# Matrix.net
KiCad netlist of a schematic drawn in Altium Designer
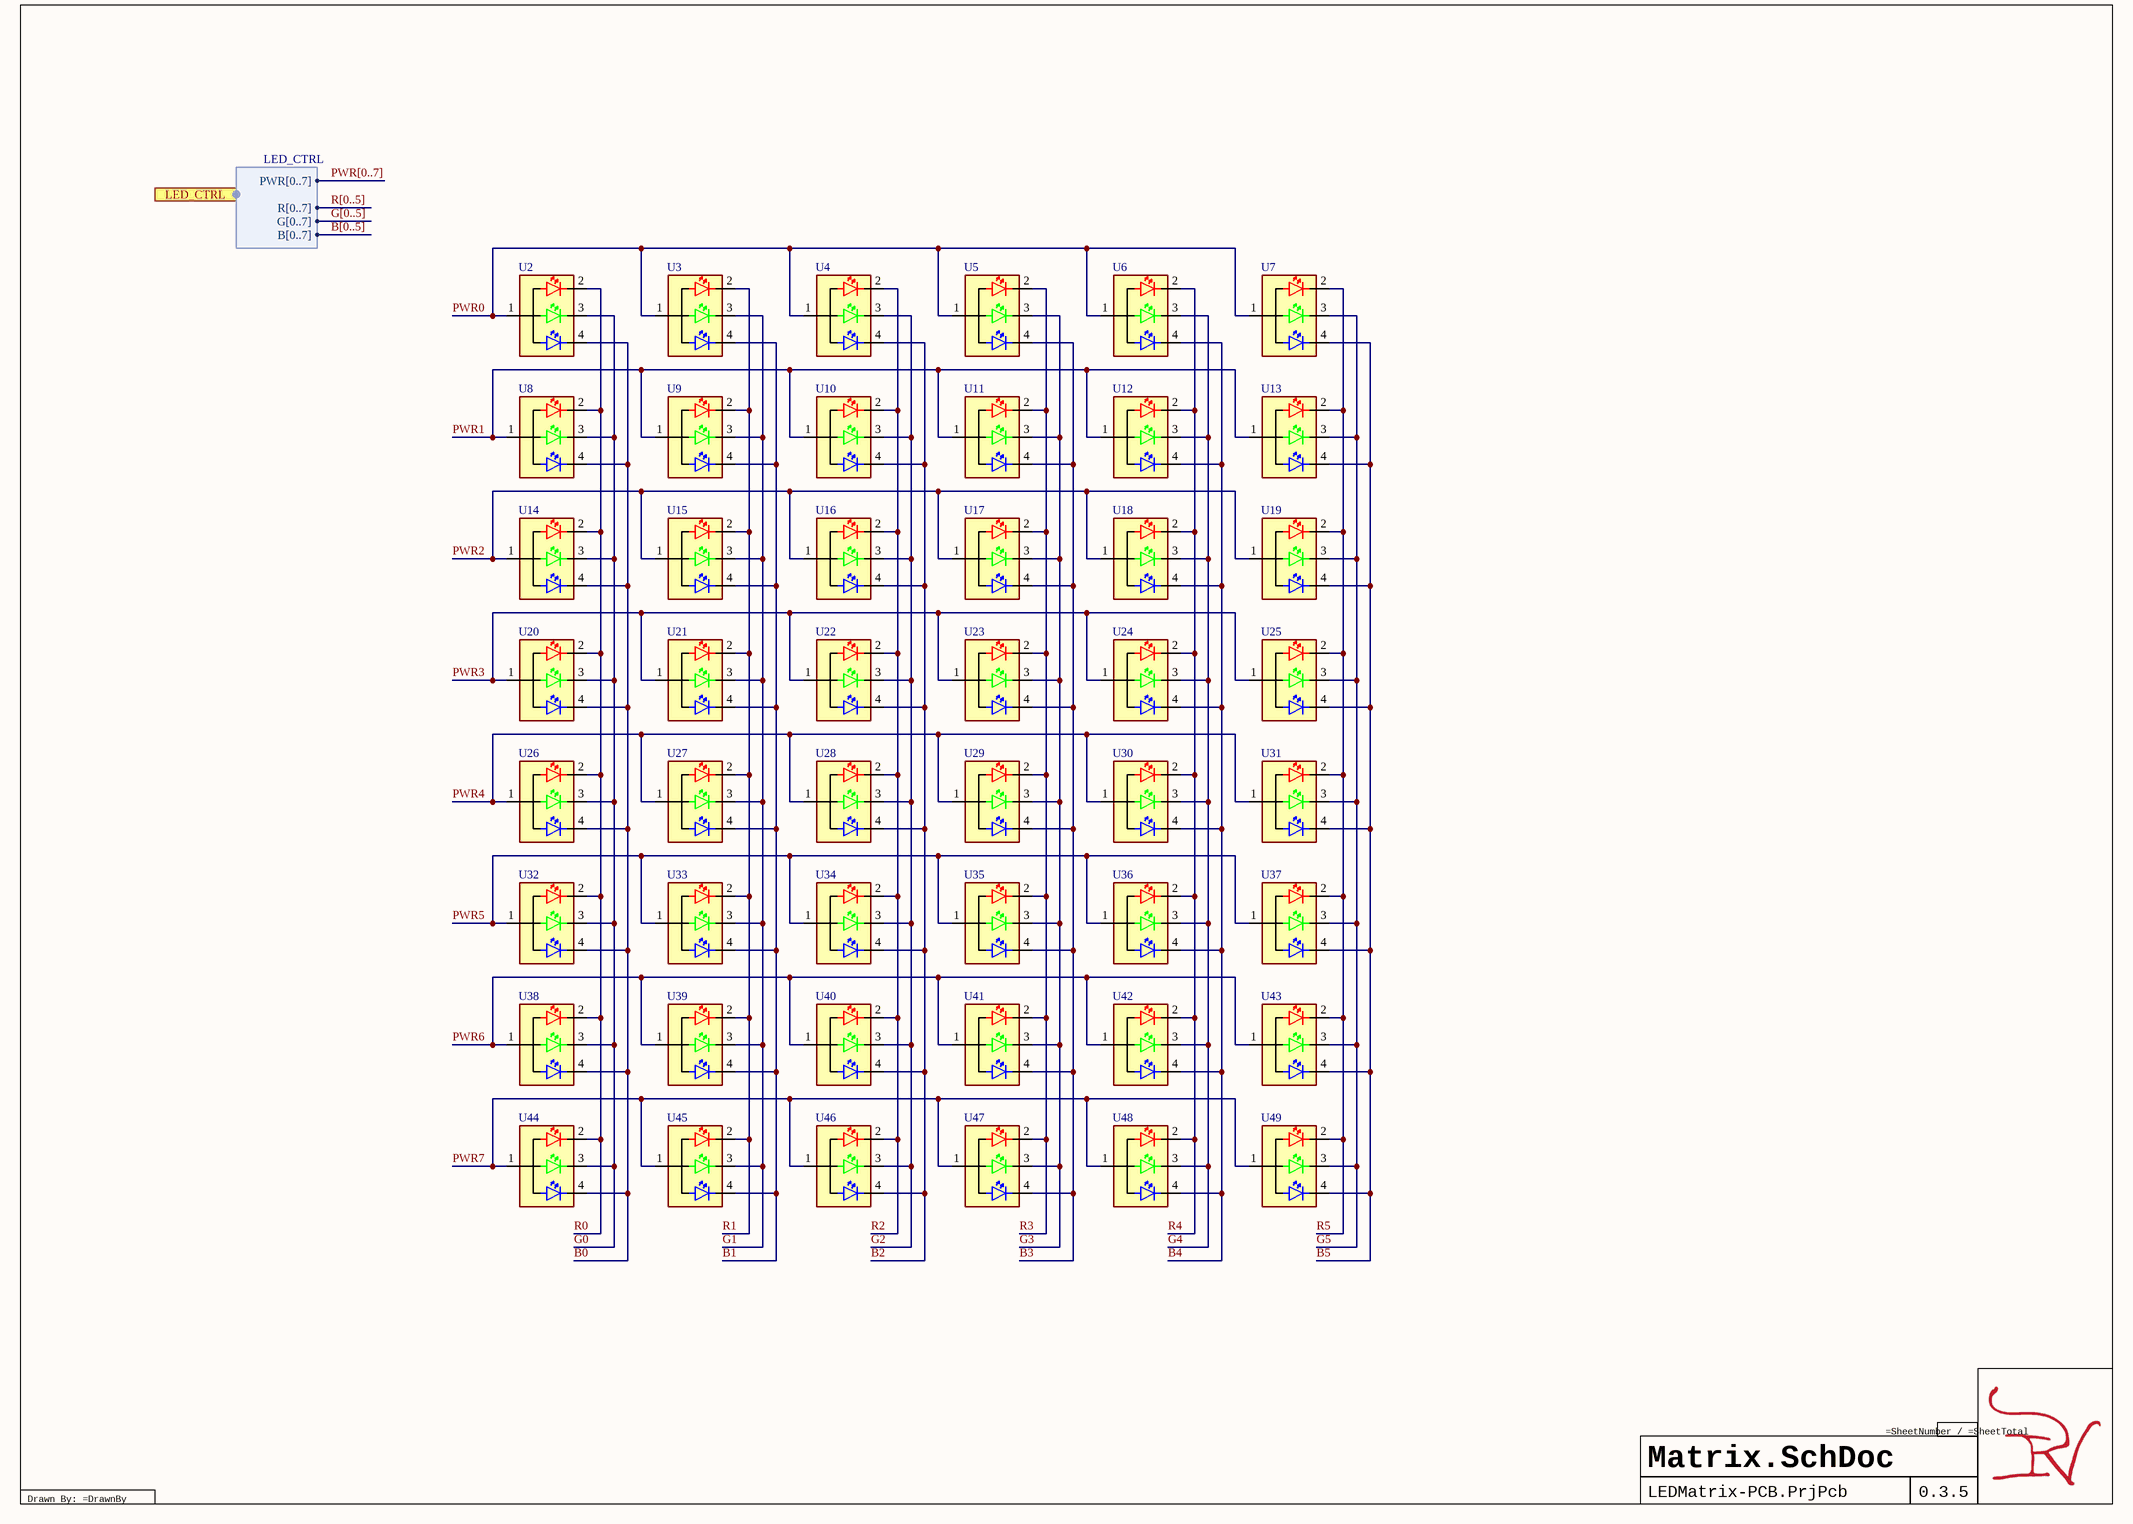
[diagram p0: Matrix.SchDoc]

(export (version "E")
  (design (tool "Eeschema 10.0.6"))
  (components
    (comp (ref "U2")
      (value "B36J3RGB-F6C0001H4U1930")
      (footprint "B36J3RGB-F6C0001H4U1930-Footprint-1")
      (description "Led Rgb Common Anode (0.65(L)X 0")
      (libsource (lib "IIT Motorsports") (part "B36J3RGB-F6C0001H4U1930-Symbol-1"))
    )
    (comp (ref "U3")
      (value "B36J3RGB-F6C0001H4U1930")
      (footprint "B36J3RGB-F6C0001H4U1930-Footprint-1")
      (description "Led Rgb Common Anode (0.65(L)X 0")
      (libsource (lib "IIT Motorsports") (part "B36J3RGB-F6C0001H4U1930-Symbol-1"))
    )
    (comp (ref "U4")
      (value "B36J3RGB-F6C0001H4U1930")
      (footprint "B36J3RGB-F6C0001H4U1930-Footprint-1")
      (description "Led Rgb Common Anode (0.65(L)X 0")
      (libsource (lib "IIT Motorsports") (part "B36J3RGB-F6C0001H4U1930-Symbol-1"))
    )
    (comp (ref "U5")
      (value "B36J3RGB-F6C0001H4U1930")
      (footprint "B36J3RGB-F6C0001H4U1930-Footprint-1")
      (description "Led Rgb Common Anode (0.65(L)X 0")
      (libsource (lib "IIT Motorsports") (part "B36J3RGB-F6C0001H4U1930-Symbol-1"))
    )
    (comp (ref "U6")
      (value "B36J3RGB-F6C0001H4U1930")
      (footprint "B36J3RGB-F6C0001H4U1930-Footprint-1")
      (description "Led Rgb Common Anode (0.65(L)X 0")
      (libsource (lib "IIT Motorsports") (part "B36J3RGB-F6C0001H4U1930-Symbol-1"))
    )
    (comp (ref "U7")
      (value "B36J3RGB-F6C0001H4U1930")
      (footprint "B36J3RGB-F6C0001H4U1930-Footprint-1")
      (description "Led Rgb Common Anode (0.65(L)X 0")
      (libsource (lib "IIT Motorsports") (part "B36J3RGB-F6C0001H4U1930-Symbol-1"))
    )
    (comp (ref "U8")
      (value "B36J3RGB-F6C0001H4U1930")
      (footprint "B36J3RGB-F6C0001H4U1930-Footprint-1")
      (description "Led Rgb Common Anode (0.65(L)X 0")
      (libsource (lib "IIT Motorsports") (part "B36J3RGB-F6C0001H4U1930-Symbol-1"))
    )
    (comp (ref "U9")
      (value "B36J3RGB-F6C0001H4U1930")
      (footprint "B36J3RGB-F6C0001H4U1930-Footprint-1")
      (description "Led Rgb Common Anode (0.65(L)X 0")
      (libsource (lib "IIT Motorsports") (part "B36J3RGB-F6C0001H4U1930-Symbol-1"))
    )
    (comp (ref "U10")
      (value "B36J3RGB-F6C0001H4U1930")
      (footprint "B36J3RGB-F6C0001H4U1930-Footprint-1")
      (description "Led Rgb Common Anode (0.65(L)X 0")
      (libsource (lib "IIT Motorsports") (part "B36J3RGB-F6C0001H4U1930-Symbol-1"))
    )
    (comp (ref "U11")
      (value "B36J3RGB-F6C0001H4U1930")
      (footprint "B36J3RGB-F6C0001H4U1930-Footprint-1")
      (description "Led Rgb Common Anode (0.65(L)X 0")
      (libsource (lib "IIT Motorsports") (part "B36J3RGB-F6C0001H4U1930-Symbol-1"))
    )
    (comp (ref "U12")
      (value "B36J3RGB-F6C0001H4U1930")
      (footprint "B36J3RGB-F6C0001H4U1930-Footprint-1")
      (description "Led Rgb Common Anode (0.65(L)X 0")
      (libsource (lib "IIT Motorsports") (part "B36J3RGB-F6C0001H4U1930-Symbol-1"))
    )
    (comp (ref "U13")
      (value "B36J3RGB-F6C0001H4U1930")
      (footprint "B36J3RGB-F6C0001H4U1930-Footprint-1")
      (description "Led Rgb Common Anode (0.65(L)X 0")
      (libsource (lib "IIT Motorsports") (part "B36J3RGB-F6C0001H4U1930-Symbol-1"))
    )
    (comp (ref "U14")
      (value "B36J3RGB-F6C0001H4U1930")
      (footprint "B36J3RGB-F6C0001H4U1930-Footprint-1")
      (description "Led Rgb Common Anode (0.65(L)X 0")
      (libsource (lib "IIT Motorsports") (part "B36J3RGB-F6C0001H4U1930-Symbol-1"))
    )
    (comp (ref "U15")
      (value "B36J3RGB-F6C0001H4U1930")
      (footprint "B36J3RGB-F6C0001H4U1930-Footprint-1")
      (description "Led Rgb Common Anode (0.65(L)X 0")
      (libsource (lib "IIT Motorsports") (part "B36J3RGB-F6C0001H4U1930-Symbol-1"))
    )
    (comp (ref "U16")
      (value "B36J3RGB-F6C0001H4U1930")
      (footprint "B36J3RGB-F6C0001H4U1930-Footprint-1")
      (description "Led Rgb Common Anode (0.65(L)X 0")
      (libsource (lib "IIT Motorsports") (part "B36J3RGB-F6C0001H4U1930-Symbol-1"))
    )
    (comp (ref "U17")
      (value "B36J3RGB-F6C0001H4U1930")
      (footprint "B36J3RGB-F6C0001H4U1930-Footprint-1")
      (description "Led Rgb Common Anode (0.65(L)X 0")
      (libsource (lib "IIT Motorsports") (part "B36J3RGB-F6C0001H4U1930-Symbol-1"))
    )
    (comp (ref "U18")
      (value "B36J3RGB-F6C0001H4U1930")
      (footprint "B36J3RGB-F6C0001H4U1930-Footprint-1")
      (description "Led Rgb Common Anode (0.65(L)X 0")
      (libsource (lib "IIT Motorsports") (part "B36J3RGB-F6C0001H4U1930-Symbol-1"))
    )
    (comp (ref "U19")
      (value "B36J3RGB-F6C0001H4U1930")
      (footprint "B36J3RGB-F6C0001H4U1930-Footprint-1")
      (description "Led Rgb Common Anode (0.65(L)X 0")
      (libsource (lib "IIT Motorsports") (part "B36J3RGB-F6C0001H4U1930-Symbol-1"))
    )
    (comp (ref "U20")
      (value "B36J3RGB-F6C0001H4U1930")
      (footprint "B36J3RGB-F6C0001H4U1930-Footprint-1")
      (description "Led Rgb Common Anode (0.65(L)X 0")
      (libsource (lib "IIT Motorsports") (part "B36J3RGB-F6C0001H4U1930-Symbol-1"))
    )
    (comp (ref "U21")
      (value "B36J3RGB-F6C0001H4U1930")
      (footprint "B36J3RGB-F6C0001H4U1930-Footprint-1")
      (description "Led Rgb Common Anode (0.65(L)X 0")
      (libsource (lib "IIT Motorsports") (part "B36J3RGB-F6C0001H4U1930-Symbol-1"))
    )
    (comp (ref "U22")
      (value "B36J3RGB-F6C0001H4U1930")
      (footprint "B36J3RGB-F6C0001H4U1930-Footprint-1")
      (description "Led Rgb Common Anode (0.65(L)X 0")
      (libsource (lib "IIT Motorsports") (part "B36J3RGB-F6C0001H4U1930-Symbol-1"))
    )
    (comp (ref "U23")
      (value "B36J3RGB-F6C0001H4U1930")
      (footprint "B36J3RGB-F6C0001H4U1930-Footprint-1")
      (description "Led Rgb Common Anode (0.65(L)X 0")
      (libsource (lib "IIT Motorsports") (part "B36J3RGB-F6C0001H4U1930-Symbol-1"))
    )
    (comp (ref "U24")
      (value "B36J3RGB-F6C0001H4U1930")
      (footprint "B36J3RGB-F6C0001H4U1930-Footprint-1")
      (description "Led Rgb Common Anode (0.65(L)X 0")
      (libsource (lib "IIT Motorsports") (part "B36J3RGB-F6C0001H4U1930-Symbol-1"))
    )
    (comp (ref "U25")
      (value "B36J3RGB-F6C0001H4U1930")
      (footprint "B36J3RGB-F6C0001H4U1930-Footprint-1")
      (description "Led Rgb Common Anode (0.65(L)X 0")
      (libsource (lib "IIT Motorsports") (part "B36J3RGB-F6C0001H4U1930-Symbol-1"))
    )
    (comp (ref "U26")
      (value "B36J3RGB-F6C0001H4U1930")
      (footprint "B36J3RGB-F6C0001H4U1930-Footprint-1")
      (description "Led Rgb Common Anode (0.65(L)X 0")
      (libsource (lib "IIT Motorsports") (part "B36J3RGB-F6C0001H4U1930-Symbol-1"))
    )
    (comp (ref "U27")
      (value "B36J3RGB-F6C0001H4U1930")
      (footprint "B36J3RGB-F6C0001H4U1930-Footprint-1")
      (description "Led Rgb Common Anode (0.65(L)X 0")
      (libsource (lib "IIT Motorsports") (part "B36J3RGB-F6C0001H4U1930-Symbol-1"))
    )
    (comp (ref "U28")
      (value "B36J3RGB-F6C0001H4U1930")
      (footprint "B36J3RGB-F6C0001H4U1930-Footprint-1")
      (description "Led Rgb Common Anode (0.65(L)X 0")
      (libsource (lib "IIT Motorsports") (part "B36J3RGB-F6C0001H4U1930-Symbol-1"))
    )
    (comp (ref "U29")
      (value "B36J3RGB-F6C0001H4U1930")
      (footprint "B36J3RGB-F6C0001H4U1930-Footprint-1")
      (description "Led Rgb Common Anode (0.65(L)X 0")
      (libsource (lib "IIT Motorsports") (part "B36J3RGB-F6C0001H4U1930-Symbol-1"))
    )
    (comp (ref "U30")
      (value "B36J3RGB-F6C0001H4U1930")
      (footprint "B36J3RGB-F6C0001H4U1930-Footprint-1")
      (description "Led Rgb Common Anode (0.65(L)X 0")
      (libsource (lib "IIT Motorsports") (part "B36J3RGB-F6C0001H4U1930-Symbol-1"))
    )
    (comp (ref "U31")
      (value "B36J3RGB-F6C0001H4U1930")
      (footprint "B36J3RGB-F6C0001H4U1930-Footprint-1")
      (description "Led Rgb Common Anode (0.65(L)X 0")
      (libsource (lib "IIT Motorsports") (part "B36J3RGB-F6C0001H4U1930-Symbol-1"))
    )
    (comp (ref "U32")
      (value "B36J3RGB-F6C0001H4U1930")
      (footprint "B36J3RGB-F6C0001H4U1930-Footprint-1")
      (description "Led Rgb Common Anode (0.65(L)X 0")
      (libsource (lib "IIT Motorsports") (part "B36J3RGB-F6C0001H4U1930-Symbol-1"))
    )
    (comp (ref "U33")
      (value "B36J3RGB-F6C0001H4U1930")
      (footprint "B36J3RGB-F6C0001H4U1930-Footprint-1")
      (description "Led Rgb Common Anode (0.65(L)X 0")
      (libsource (lib "IIT Motorsports") (part "B36J3RGB-F6C0001H4U1930-Symbol-1"))
    )
    (comp (ref "U34")
      (value "B36J3RGB-F6C0001H4U1930")
      (footprint "B36J3RGB-F6C0001H4U1930-Footprint-1")
      (description "Led Rgb Common Anode (0.65(L)X 0")
      (libsource (lib "IIT Motorsports") (part "B36J3RGB-F6C0001H4U1930-Symbol-1"))
    )
    (comp (ref "U35")
      (value "B36J3RGB-F6C0001H4U1930")
      (footprint "B36J3RGB-F6C0001H4U1930-Footprint-1")
      (description "Led Rgb Common Anode (0.65(L)X 0")
      (libsource (lib "IIT Motorsports") (part "B36J3RGB-F6C0001H4U1930-Symbol-1"))
    )
    (comp (ref "U36")
      (value "B36J3RGB-F6C0001H4U1930")
      (footprint "B36J3RGB-F6C0001H4U1930-Footprint-1")
      (description "Led Rgb Common Anode (0.65(L)X 0")
      (libsource (lib "IIT Motorsports") (part "B36J3RGB-F6C0001H4U1930-Symbol-1"))
    )
    (comp (ref "U37")
      (value "B36J3RGB-F6C0001H4U1930")
      (footprint "B36J3RGB-F6C0001H4U1930-Footprint-1")
      (description "Led Rgb Common Anode (0.65(L)X 0")
      (libsource (lib "IIT Motorsports") (part "B36J3RGB-F6C0001H4U1930-Symbol-1"))
    )
    (comp (ref "U38")
      (value "B36J3RGB-F6C0001H4U1930")
      (footprint "B36J3RGB-F6C0001H4U1930-Footprint-1")
      (description "Led Rgb Common Anode (0.65(L)X 0")
      (libsource (lib "IIT Motorsports") (part "B36J3RGB-F6C0001H4U1930-Symbol-1"))
    )
    (comp (ref "U39")
      (value "B36J3RGB-F6C0001H4U1930")
      (footprint "B36J3RGB-F6C0001H4U1930-Footprint-1")
      (description "Led Rgb Common Anode (0.65(L)X 0")
      (libsource (lib "IIT Motorsports") (part "B36J3RGB-F6C0001H4U1930-Symbol-1"))
    )
    (comp (ref "U40")
      (value "B36J3RGB-F6C0001H4U1930")
      (footprint "B36J3RGB-F6C0001H4U1930-Footprint-1")
      (description "Led Rgb Common Anode (0.65(L)X 0")
      (libsource (lib "IIT Motorsports") (part "B36J3RGB-F6C0001H4U1930-Symbol-1"))
    )
    (comp (ref "U41")
      (value "B36J3RGB-F6C0001H4U1930")
      (footprint "B36J3RGB-F6C0001H4U1930-Footprint-1")
      (description "Led Rgb Common Anode (0.65(L)X 0")
      (libsource (lib "IIT Motorsports") (part "B36J3RGB-F6C0001H4U1930-Symbol-1"))
    )
    (comp (ref "U42")
      (value "B36J3RGB-F6C0001H4U1930")
      (footprint "B36J3RGB-F6C0001H4U1930-Footprint-1")
      (description "Led Rgb Common Anode (0.65(L)X 0")
      (libsource (lib "IIT Motorsports") (part "B36J3RGB-F6C0001H4U1930-Symbol-1"))
    )
    (comp (ref "U43")
      (value "B36J3RGB-F6C0001H4U1930")
      (footprint "B36J3RGB-F6C0001H4U1930-Footprint-1")
      (description "Led Rgb Common Anode (0.65(L)X 0")
      (libsource (lib "IIT Motorsports") (part "B36J3RGB-F6C0001H4U1930-Symbol-1"))
    )
    (comp (ref "U44")
      (value "B36J3RGB-F6C0001H4U1930")
      (footprint "B36J3RGB-F6C0001H4U1930-Footprint-1")
      (description "Led Rgb Common Anode (0.65(L)X 0")
      (libsource (lib "IIT Motorsports") (part "B36J3RGB-F6C0001H4U1930-Symbol-1"))
    )
    (comp (ref "U45")
      (value "B36J3RGB-F6C0001H4U1930")
      (footprint "B36J3RGB-F6C0001H4U1930-Footprint-1")
      (description "Led Rgb Common Anode (0.65(L)X 0")
      (libsource (lib "IIT Motorsports") (part "B36J3RGB-F6C0001H4U1930-Symbol-1"))
    )
    (comp (ref "U46")
      (value "B36J3RGB-F6C0001H4U1930")
      (footprint "B36J3RGB-F6C0001H4U1930-Footprint-1")
      (description "Led Rgb Common Anode (0.65(L)X 0")
      (libsource (lib "IIT Motorsports") (part "B36J3RGB-F6C0001H4U1930-Symbol-1"))
    )
    (comp (ref "U47")
      (value "B36J3RGB-F6C0001H4U1930")
      (footprint "B36J3RGB-F6C0001H4U1930-Footprint-1")
      (description "Led Rgb Common Anode (0.65(L)X 0")
      (libsource (lib "IIT Motorsports") (part "B36J3RGB-F6C0001H4U1930-Symbol-1"))
    )
    (comp (ref "U48")
      (value "B36J3RGB-F6C0001H4U1930")
      (footprint "B36J3RGB-F6C0001H4U1930-Footprint-1")
      (description "Led Rgb Common Anode (0.65(L)X 0")
      (libsource (lib "IIT Motorsports") (part "B36J3RGB-F6C0001H4U1930-Symbol-1"))
    )
    (comp (ref "U49")
      (value "B36J3RGB-F6C0001H4U1930")
      (footprint "B36J3RGB-F6C0001H4U1930-Footprint-1")
      (description "Led Rgb Common Anode (0.65(L)X 0")
      (libsource (lib "IIT Motorsports") (part "B36J3RGB-F6C0001H4U1930-Symbol-1"))
    )
  )
  (nets
    (net (code "2") (name "/B0") (class "Default")
      (node (ref "U14") (pin "4") (pinfunction "4_4") (pintype "passive"))
      (node (ref "U2") (pin "4") (pinfunction "4_4") (pintype "passive"))
      (node (ref "U20") (pin "4") (pinfunction "4_4") (pintype "passive"))
      (node (ref "U26") (pin "4") (pinfunction "4_4") (pintype "passive"))
      (node (ref "U32") (pin "4") (pinfunction "4_4") (pintype "passive"))
      (node (ref "U38") (pin "4") (pinfunction "4_4") (pintype "passive"))
      (node (ref "U44") (pin "4") (pinfunction "4_4") (pintype "passive"))
      (node (ref "U8") (pin "4") (pinfunction "4_4") (pintype "passive"))
    )
    (net (code "3") (name "/B1") (class "Default")
      (node (ref "U15") (pin "4") (pinfunction "4_4") (pintype "passive"))
      (node (ref "U21") (pin "4") (pinfunction "4_4") (pintype "passive"))
      (node (ref "U27") (pin "4") (pinfunction "4_4") (pintype "passive"))
      (node (ref "U3") (pin "4") (pinfunction "4_4") (pintype "passive"))
      (node (ref "U33") (pin "4") (pinfunction "4_4") (pintype "passive"))
      (node (ref "U39") (pin "4") (pinfunction "4_4") (pintype "passive"))
      (node (ref "U45") (pin "4") (pinfunction "4_4") (pintype "passive"))
      (node (ref "U9") (pin "4") (pinfunction "4_4") (pintype "passive"))
    )
    (net (code "4") (name "/B2") (class "Default")
      (node (ref "U10") (pin "4") (pinfunction "4_4") (pintype "passive"))
      (node (ref "U16") (pin "4") (pinfunction "4_4") (pintype "passive"))
      (node (ref "U22") (pin "4") (pinfunction "4_4") (pintype "passive"))
      (node (ref "U28") (pin "4") (pinfunction "4_4") (pintype "passive"))
      (node (ref "U34") (pin "4") (pinfunction "4_4") (pintype "passive"))
      (node (ref "U4") (pin "4") (pinfunction "4_4") (pintype "passive"))
      (node (ref "U40") (pin "4") (pinfunction "4_4") (pintype "passive"))
      (node (ref "U46") (pin "4") (pinfunction "4_4") (pintype "passive"))
    )
    (net (code "5") (name "/B3") (class "Default")
      (node (ref "U11") (pin "4") (pinfunction "4_4") (pintype "passive"))
      (node (ref "U17") (pin "4") (pinfunction "4_4") (pintype "passive"))
      (node (ref "U23") (pin "4") (pinfunction "4_4") (pintype "passive"))
      (node (ref "U29") (pin "4") (pinfunction "4_4") (pintype "passive"))
      (node (ref "U35") (pin "4") (pinfunction "4_4") (pintype "passive"))
      (node (ref "U41") (pin "4") (pinfunction "4_4") (pintype "passive"))
      (node (ref "U47") (pin "4") (pinfunction "4_4") (pintype "passive"))
      (node (ref "U5") (pin "4") (pinfunction "4_4") (pintype "passive"))
    )
    (net (code "6") (name "/B4") (class "Default")
      (node (ref "U12") (pin "4") (pinfunction "4_4") (pintype "passive"))
      (node (ref "U18") (pin "4") (pinfunction "4_4") (pintype "passive"))
      (node (ref "U24") (pin "4") (pinfunction "4_4") (pintype "passive"))
      (node (ref "U30") (pin "4") (pinfunction "4_4") (pintype "passive"))
      (node (ref "U36") (pin "4") (pinfunction "4_4") (pintype "passive"))
      (node (ref "U42") (pin "4") (pinfunction "4_4") (pintype "passive"))
      (node (ref "U48") (pin "4") (pinfunction "4_4") (pintype "passive"))
      (node (ref "U6") (pin "4") (pinfunction "4_4") (pintype "passive"))
    )
    (net (code "7") (name "/B5") (class "Default")
      (node (ref "U13") (pin "4") (pinfunction "4_4") (pintype "passive"))
      (node (ref "U19") (pin "4") (pinfunction "4_4") (pintype "passive"))
      (node (ref "U25") (pin "4") (pinfunction "4_4") (pintype "passive"))
      (node (ref "U31") (pin "4") (pinfunction "4_4") (pintype "passive"))
      (node (ref "U37") (pin "4") (pinfunction "4_4") (pintype "passive"))
      (node (ref "U43") (pin "4") (pinfunction "4_4") (pintype "passive"))
      (node (ref "U49") (pin "4") (pinfunction "4_4") (pintype "passive"))
      (node (ref "U7") (pin "4") (pinfunction "4_4") (pintype "passive"))
    )
    (net (code "9") (name "/G0") (class "Default")
      (node (ref "U14") (pin "3") (pinfunction "3_3") (pintype "passive"))
      (node (ref "U2") (pin "3") (pinfunction "3_3") (pintype "passive"))
      (node (ref "U20") (pin "3") (pinfunction "3_3") (pintype "passive"))
      (node (ref "U26") (pin "3") (pinfunction "3_3") (pintype "passive"))
      (node (ref "U32") (pin "3") (pinfunction "3_3") (pintype "passive"))
      (node (ref "U38") (pin "3") (pinfunction "3_3") (pintype "passive"))
      (node (ref "U44") (pin "3") (pinfunction "3_3") (pintype "passive"))
      (node (ref "U8") (pin "3") (pinfunction "3_3") (pintype "passive"))
    )
    (net (code "10") (name "/G1") (class "Default")
      (node (ref "U15") (pin "3") (pinfunction "3_3") (pintype "passive"))
      (node (ref "U21") (pin "3") (pinfunction "3_3") (pintype "passive"))
      (node (ref "U27") (pin "3") (pinfunction "3_3") (pintype "passive"))
      (node (ref "U3") (pin "3") (pinfunction "3_3") (pintype "passive"))
      (node (ref "U33") (pin "3") (pinfunction "3_3") (pintype "passive"))
      (node (ref "U39") (pin "3") (pinfunction "3_3") (pintype "passive"))
      (node (ref "U45") (pin "3") (pinfunction "3_3") (pintype "passive"))
      (node (ref "U9") (pin "3") (pinfunction "3_3") (pintype "passive"))
    )
    (net (code "11") (name "/G2") (class "Default")
      (node (ref "U10") (pin "3") (pinfunction "3_3") (pintype "passive"))
      (node (ref "U16") (pin "3") (pinfunction "3_3") (pintype "passive"))
      (node (ref "U22") (pin "3") (pinfunction "3_3") (pintype "passive"))
      (node (ref "U28") (pin "3") (pinfunction "3_3") (pintype "passive"))
      (node (ref "U34") (pin "3") (pinfunction "3_3") (pintype "passive"))
      (node (ref "U4") (pin "3") (pinfunction "3_3") (pintype "passive"))
      (node (ref "U40") (pin "3") (pinfunction "3_3") (pintype "passive"))
      (node (ref "U46") (pin "3") (pinfunction "3_3") (pintype "passive"))
    )
    (net (code "12") (name "/G3") (class "Default")
      (node (ref "U11") (pin "3") (pinfunction "3_3") (pintype "passive"))
      (node (ref "U17") (pin "3") (pinfunction "3_3") (pintype "passive"))
      (node (ref "U23") (pin "3") (pinfunction "3_3") (pintype "passive"))
      (node (ref "U29") (pin "3") (pinfunction "3_3") (pintype "passive"))
      (node (ref "U35") (pin "3") (pinfunction "3_3") (pintype "passive"))
      (node (ref "U41") (pin "3") (pinfunction "3_3") (pintype "passive"))
      (node (ref "U47") (pin "3") (pinfunction "3_3") (pintype "passive"))
      (node (ref "U5") (pin "3") (pinfunction "3_3") (pintype "passive"))
    )
    (net (code "13") (name "/G4") (class "Default")
      (node (ref "U12") (pin "3") (pinfunction "3_3") (pintype "passive"))
      (node (ref "U18") (pin "3") (pinfunction "3_3") (pintype "passive"))
      (node (ref "U24") (pin "3") (pinfunction "3_3") (pintype "passive"))
      (node (ref "U30") (pin "3") (pinfunction "3_3") (pintype "passive"))
      (node (ref "U36") (pin "3") (pinfunction "3_3") (pintype "passive"))
      (node (ref "U42") (pin "3") (pinfunction "3_3") (pintype "passive"))
      (node (ref "U48") (pin "3") (pinfunction "3_3") (pintype "passive"))
      (node (ref "U6") (pin "3") (pinfunction "3_3") (pintype "passive"))
    )
    (net (code "14") (name "/G5") (class "Default")
      (node (ref "U13") (pin "3") (pinfunction "3_3") (pintype "passive"))
      (node (ref "U19") (pin "3") (pinfunction "3_3") (pintype "passive"))
      (node (ref "U25") (pin "3") (pinfunction "3_3") (pintype "passive"))
      (node (ref "U31") (pin "3") (pinfunction "3_3") (pintype "passive"))
      (node (ref "U37") (pin "3") (pinfunction "3_3") (pintype "passive"))
      (node (ref "U43") (pin "3") (pinfunction "3_3") (pintype "passive"))
      (node (ref "U49") (pin "3") (pinfunction "3_3") (pintype "passive"))
      (node (ref "U7") (pin "3") (pinfunction "3_3") (pintype "passive"))
    )
    (net (code "17") (name "/PWR0") (class "Default")
      (node (ref "U2") (pin "1") (pinfunction "1_1") (pintype "passive"))
      (node (ref "U3") (pin "1") (pinfunction "1_1") (pintype "passive"))
      (node (ref "U4") (pin "1") (pinfunction "1_1") (pintype "passive"))
      (node (ref "U5") (pin "1") (pinfunction "1_1") (pintype "passive"))
      (node (ref "U6") (pin "1") (pinfunction "1_1") (pintype "passive"))
      (node (ref "U7") (pin "1") (pinfunction "1_1") (pintype "passive"))
    )
    (net (code "18") (name "/PWR1") (class "Default")
      (node (ref "U10") (pin "1") (pinfunction "1_1") (pintype "passive"))
      (node (ref "U11") (pin "1") (pinfunction "1_1") (pintype "passive"))
      (node (ref "U12") (pin "1") (pinfunction "1_1") (pintype "passive"))
      (node (ref "U13") (pin "1") (pinfunction "1_1") (pintype "passive"))
      (node (ref "U8") (pin "1") (pinfunction "1_1") (pintype "passive"))
      (node (ref "U9") (pin "1") (pinfunction "1_1") (pintype "passive"))
    )
    (net (code "19") (name "/PWR2") (class "Default")
      (node (ref "U14") (pin "1") (pinfunction "1_1") (pintype "passive"))
      (node (ref "U15") (pin "1") (pinfunction "1_1") (pintype "passive"))
      (node (ref "U16") (pin "1") (pinfunction "1_1") (pintype "passive"))
      (node (ref "U17") (pin "1") (pinfunction "1_1") (pintype "passive"))
      (node (ref "U18") (pin "1") (pinfunction "1_1") (pintype "passive"))
      (node (ref "U19") (pin "1") (pinfunction "1_1") (pintype "passive"))
    )
    (net (code "20") (name "/PWR3") (class "Default")
      (node (ref "U20") (pin "1") (pinfunction "1_1") (pintype "passive"))
      (node (ref "U21") (pin "1") (pinfunction "1_1") (pintype "passive"))
      (node (ref "U22") (pin "1") (pinfunction "1_1") (pintype "passive"))
      (node (ref "U23") (pin "1") (pinfunction "1_1") (pintype "passive"))
      (node (ref "U24") (pin "1") (pinfunction "1_1") (pintype "passive"))
      (node (ref "U25") (pin "1") (pinfunction "1_1") (pintype "passive"))
    )
    (net (code "21") (name "/PWR4") (class "Default")
      (node (ref "U26") (pin "1") (pinfunction "1_1") (pintype "passive"))
      (node (ref "U27") (pin "1") (pinfunction "1_1") (pintype "passive"))
      (node (ref "U28") (pin "1") (pinfunction "1_1") (pintype "passive"))
      (node (ref "U29") (pin "1") (pinfunction "1_1") (pintype "passive"))
      (node (ref "U30") (pin "1") (pinfunction "1_1") (pintype "passive"))
      (node (ref "U31") (pin "1") (pinfunction "1_1") (pintype "passive"))
    )
    (net (code "22") (name "/PWR5") (class "Default")
      (node (ref "U32") (pin "1") (pinfunction "1_1") (pintype "passive"))
      (node (ref "U33") (pin "1") (pinfunction "1_1") (pintype "passive"))
      (node (ref "U34") (pin "1") (pinfunction "1_1") (pintype "passive"))
      (node (ref "U35") (pin "1") (pinfunction "1_1") (pintype "passive"))
      (node (ref "U36") (pin "1") (pinfunction "1_1") (pintype "passive"))
      (node (ref "U37") (pin "1") (pinfunction "1_1") (pintype "passive"))
    )
    (net (code "23") (name "/PWR6") (class "Default")
      (node (ref "U38") (pin "1") (pinfunction "1_1") (pintype "passive"))
      (node (ref "U39") (pin "1") (pinfunction "1_1") (pintype "passive"))
      (node (ref "U40") (pin "1") (pinfunction "1_1") (pintype "passive"))
      (node (ref "U41") (pin "1") (pinfunction "1_1") (pintype "passive"))
      (node (ref "U42") (pin "1") (pinfunction "1_1") (pintype "passive"))
      (node (ref "U43") (pin "1") (pinfunction "1_1") (pintype "passive"))
    )
    (net (code "24") (name "/PWR7") (class "Default")
      (node (ref "U44") (pin "1") (pinfunction "1_1") (pintype "passive"))
      (node (ref "U45") (pin "1") (pinfunction "1_1") (pintype "passive"))
      (node (ref "U46") (pin "1") (pinfunction "1_1") (pintype "passive"))
      (node (ref "U47") (pin "1") (pinfunction "1_1") (pintype "passive"))
      (node (ref "U48") (pin "1") (pinfunction "1_1") (pintype "passive"))
      (node (ref "U49") (pin "1") (pinfunction "1_1") (pintype "passive"))
    )
    (net (code "25") (name "/R0") (class "Default")
      (node (ref "U14") (pin "2") (pinfunction "2_2") (pintype "passive"))
      (node (ref "U2") (pin "2") (pinfunction "2_2") (pintype "passive"))
      (node (ref "U20") (pin "2") (pinfunction "2_2") (pintype "passive"))
      (node (ref "U26") (pin "2") (pinfunction "2_2") (pintype "passive"))
      (node (ref "U32") (pin "2") (pinfunction "2_2") (pintype "passive"))
      (node (ref "U38") (pin "2") (pinfunction "2_2") (pintype "passive"))
      (node (ref "U44") (pin "2") (pinfunction "2_2") (pintype "passive"))
      (node (ref "U8") (pin "2") (pinfunction "2_2") (pintype "passive"))
    )
    (net (code "26") (name "/R1") (class "Default")
      (node (ref "U15") (pin "2") (pinfunction "2_2") (pintype "passive"))
      (node (ref "U21") (pin "2") (pinfunction "2_2") (pintype "passive"))
      (node (ref "U27") (pin "2") (pinfunction "2_2") (pintype "passive"))
      (node (ref "U3") (pin "2") (pinfunction "2_2") (pintype "passive"))
      (node (ref "U33") (pin "2") (pinfunction "2_2") (pintype "passive"))
      (node (ref "U39") (pin "2") (pinfunction "2_2") (pintype "passive"))
      (node (ref "U45") (pin "2") (pinfunction "2_2") (pintype "passive"))
      (node (ref "U9") (pin "2") (pinfunction "2_2") (pintype "passive"))
    )
    (net (code "27") (name "/R2") (class "Default")
      (node (ref "U10") (pin "2") (pinfunction "2_2") (pintype "passive"))
      (node (ref "U16") (pin "2") (pinfunction "2_2") (pintype "passive"))
      (node (ref "U22") (pin "2") (pinfunction "2_2") (pintype "passive"))
      (node (ref "U28") (pin "2") (pinfunction "2_2") (pintype "passive"))
      (node (ref "U34") (pin "2") (pinfunction "2_2") (pintype "passive"))
      (node (ref "U4") (pin "2") (pinfunction "2_2") (pintype "passive"))
      (node (ref "U40") (pin "2") (pinfunction "2_2") (pintype "passive"))
      (node (ref "U46") (pin "2") (pinfunction "2_2") (pintype "passive"))
    )
    (net (code "28") (name "/R3") (class "Default")
      (node (ref "U11") (pin "2") (pinfunction "2_2") (pintype "passive"))
      (node (ref "U17") (pin "2") (pinfunction "2_2") (pintype "passive"))
      (node (ref "U23") (pin "2") (pinfunction "2_2") (pintype "passive"))
      (node (ref "U29") (pin "2") (pinfunction "2_2") (pintype "passive"))
      (node (ref "U35") (pin "2") (pinfunction "2_2") (pintype "passive"))
      (node (ref "U41") (pin "2") (pinfunction "2_2") (pintype "passive"))
      (node (ref "U47") (pin "2") (pinfunction "2_2") (pintype "passive"))
      (node (ref "U5") (pin "2") (pinfunction "2_2") (pintype "passive"))
    )
    (net (code "29") (name "/R4") (class "Default")
      (node (ref "U12") (pin "2") (pinfunction "2_2") (pintype "passive"))
      (node (ref "U18") (pin "2") (pinfunction "2_2") (pintype "passive"))
      (node (ref "U24") (pin "2") (pinfunction "2_2") (pintype "passive"))
      (node (ref "U30") (pin "2") (pinfunction "2_2") (pintype "passive"))
      (node (ref "U36") (pin "2") (pinfunction "2_2") (pintype "passive"))
      (node (ref "U42") (pin "2") (pinfunction "2_2") (pintype "passive"))
      (node (ref "U48") (pin "2") (pinfunction "2_2") (pintype "passive"))
      (node (ref "U6") (pin "2") (pinfunction "2_2") (pintype "passive"))
    )
    (net (code "30") (name "/R5") (class "Default")
      (node (ref "U13") (pin "2") (pinfunction "2_2") (pintype "passive"))
      (node (ref "U19") (pin "2") (pinfunction "2_2") (pintype "passive"))
      (node (ref "U25") (pin "2") (pinfunction "2_2") (pintype "passive"))
      (node (ref "U31") (pin "2") (pinfunction "2_2") (pintype "passive"))
      (node (ref "U37") (pin "2") (pinfunction "2_2") (pintype "passive"))
      (node (ref "U43") (pin "2") (pinfunction "2_2") (pintype "passive"))
      (node (ref "U49") (pin "2") (pinfunction "2_2") (pintype "passive"))
      (node (ref "U7") (pin "2") (pinfunction "2_2") (pintype "passive"))
    )
  )
)
